# controller_board.net
KiCad netlist of a schematic drawn in EAGLE
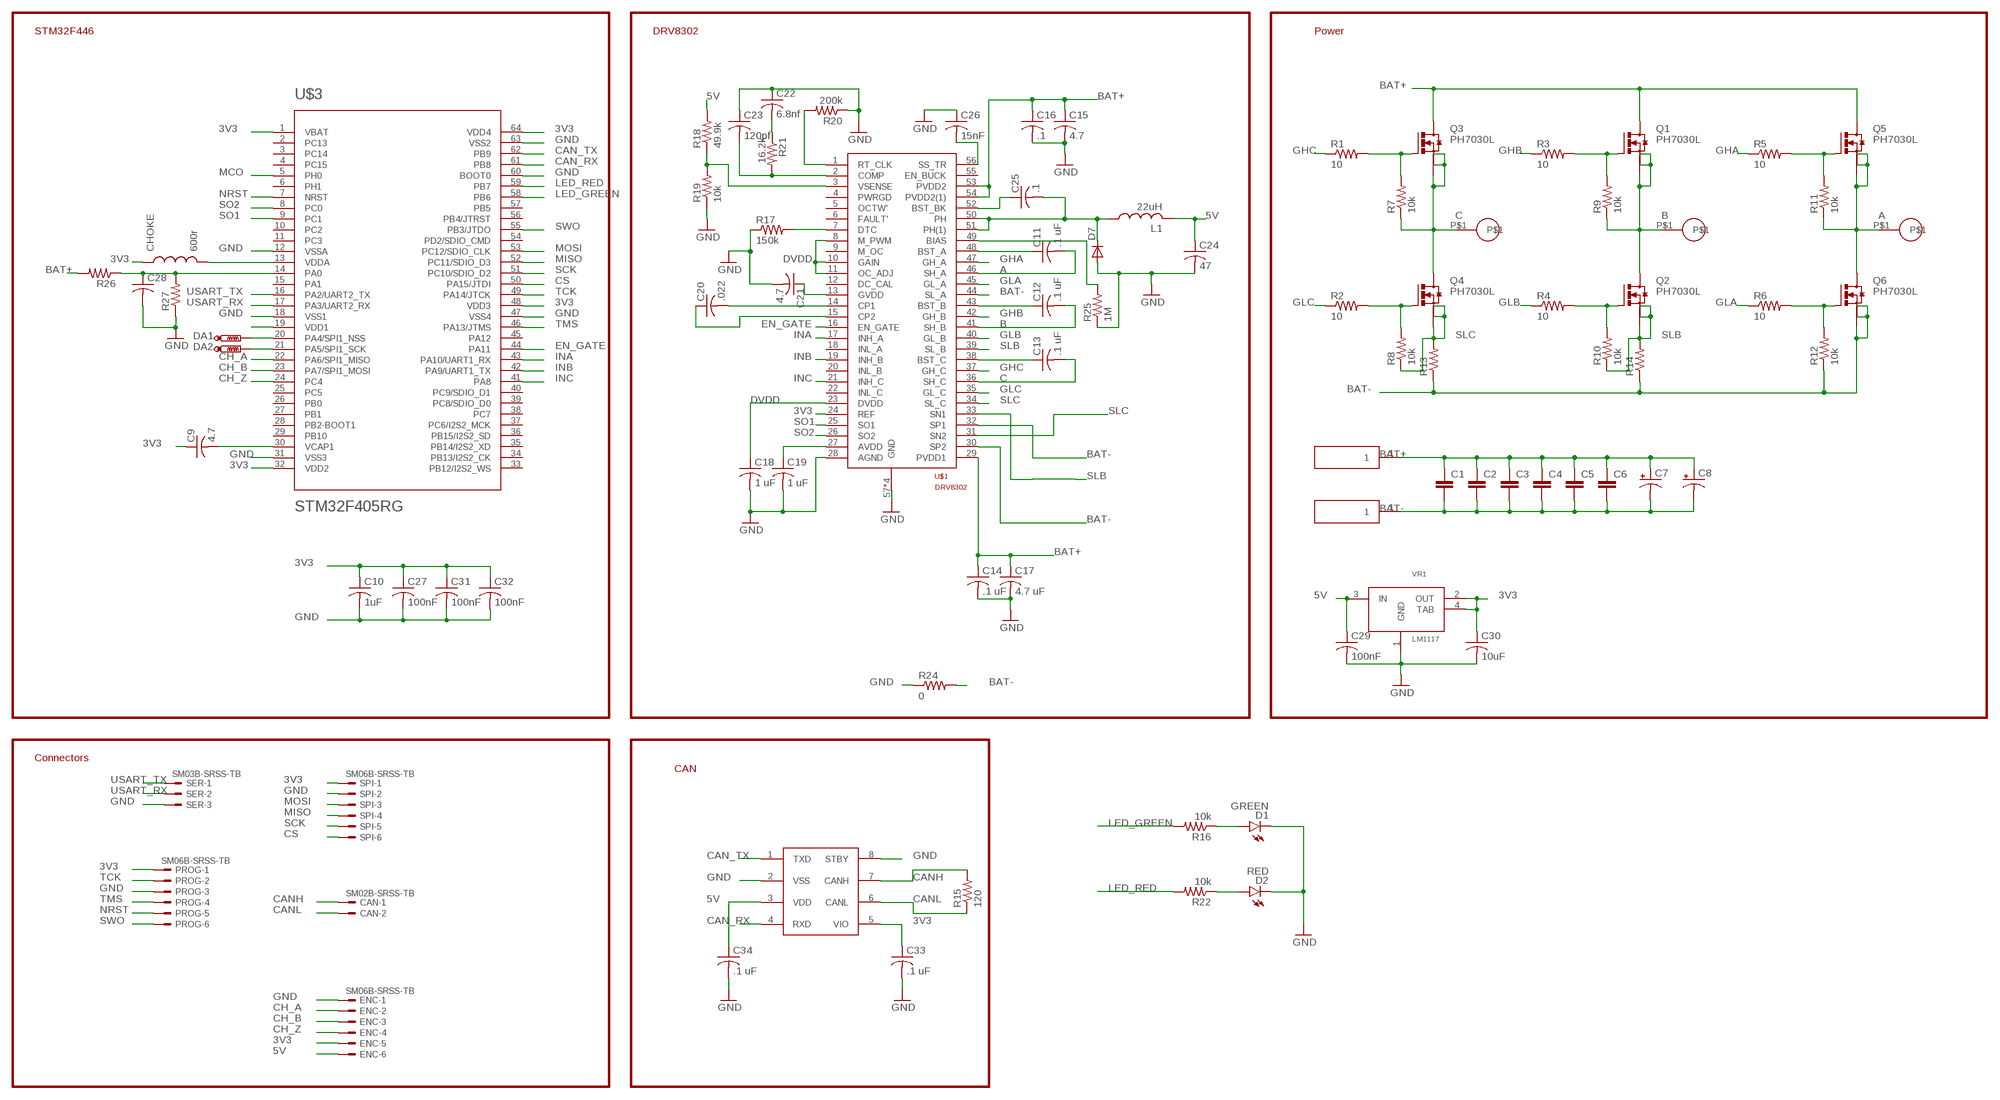
[diagram p0: schematic, sheet 1]

(export (version "E")
  (design (tool "Eeschema 10.0.6"))
  (components
    (comp (ref "C1")
      (value "C-EUC0805")
      (footprint "eagle-import:C0805")
      (libsource (lib "eagle-import") (part "C-EUC0805"))
    )
    (comp (ref "C2")
      (value "C-EUC0805")
      (footprint "eagle-import:C0805")
      (libsource (lib "eagle-import") (part "C-EUC0805"))
    )
    (comp (ref "C3")
      (value "C-EUC0805")
      (footprint "eagle-import:C0805")
      (libsource (lib "eagle-import") (part "C-EUC0805"))
    )
    (comp (ref "C4")
      (value "C-EUC0805")
      (footprint "eagle-import:C0805")
      (libsource (lib "eagle-import") (part "C-EUC0805"))
    )
    (comp (ref "C5")
      (value "C-EUC0805")
      (footprint "eagle-import:C0805")
      (libsource (lib "eagle-import") (part "C-EUC0805"))
    )
    (comp (ref "C6")
      (value "C-EUC0805")
      (footprint "eagle-import:C0805")
      (libsource (lib "eagle-import") (part "C-EUC0805"))
    )
    (comp (ref "C7")
      (value "CPOL-USE3.5-8")
      (footprint "eagle-import:E3,5-8")
      (libsource (lib "eagle-import") (part "CPOL-USE3.5-8"))
    )
    (comp (ref "C8")
      (value "CPOL-USE3.5-8")
      (footprint "eagle-import:E3,5-8")
      (libsource (lib "eagle-import") (part "CPOL-USE3.5-8"))
    )
    (comp (ref "C9")
      (value "4.7")
      (footprint "eagle-import:C0603")
      (libsource (lib "eagle-import") (part "C-USC0603"))
    )
    (comp (ref "C10")
      (value "1uF")
      (footprint "eagle-import:C0603")
      (libsource (lib "eagle-import") (part "C-USC0603"))
    )
    (comp (ref "C11")
      (value ".1 uF")
      (footprint "eagle-import:C0603")
      (libsource (lib "eagle-import") (part "C-USC0603"))
    )
    (comp (ref "C12")
      (value ".1 uF")
      (footprint "eagle-import:C0603")
      (libsource (lib "eagle-import") (part "C-USC0603"))
    )
    (comp (ref "C13")
      (value ".1 uF")
      (footprint "eagle-import:C0603")
      (libsource (lib "eagle-import") (part "C-USC0603"))
    )
    (comp (ref "C14")
      (value ".1 uF")
      (footprint "eagle-import:C0603")
      (libsource (lib "eagle-import") (part "C-USC0603"))
    )
    (comp (ref "C15")
      (value "4.7")
      (footprint "eagle-import:C0805")
      (libsource (lib "eagle-import") (part "C-USC0805"))
    )
    (comp (ref "C16")
      (value ".1")
      (footprint "eagle-import:C0603")
      (libsource (lib "eagle-import") (part "C-USC0603"))
    )
    (comp (ref "C17")
      (value "4.7 uF")
      (footprint "eagle-import:C0805")
      (libsource (lib "eagle-import") (part "C-USC0805"))
    )
    (comp (ref "C18")
      (value "1 uF")
      (footprint "eagle-import:C0603")
      (libsource (lib "eagle-import") (part "C-USC0603"))
    )
    (comp (ref "C19")
      (value "1 uF")
      (footprint "eagle-import:C0603")
      (libsource (lib "eagle-import") (part "C-USC0603"))
    )
    (comp (ref "C20")
      (value ".022")
      (footprint "eagle-import:C0603")
      (libsource (lib "eagle-import") (part "C-USC0603"))
    )
    (comp (ref "C21")
      (value "4.7")
      (footprint "eagle-import:C0805")
      (libsource (lib "eagle-import") (part "C-USC0805"))
    )
    (comp (ref "C22")
      (value "6.8nf")
      (footprint "eagle-import:C0603")
      (libsource (lib "eagle-import") (part "C-USC0603"))
    )
    (comp (ref "C23")
      (value "120pf")
      (footprint "eagle-import:C0603")
      (libsource (lib "eagle-import") (part "C-USC0603"))
    )
    (comp (ref "C24")
      (value "47")
      (footprint "eagle-import:C1210")
      (libsource (lib "eagle-import") (part "C-USC1210"))
    )
    (comp (ref "C25")
      (value ".1")
      (footprint "eagle-import:C0603")
      (libsource (lib "eagle-import") (part "C-USC0603"))
    )
    (comp (ref "C26")
      (value "15nF")
      (footprint "eagle-import:C0603")
      (libsource (lib "eagle-import") (part "C-USC0603"))
    )
    (comp (ref "C27")
      (value "100nF")
      (footprint "eagle-import:C0603")
      (libsource (lib "eagle-import") (part "C-USC0603"))
    )
    (comp (ref "C28")
      (value "C-USC0603")
      (footprint "eagle-import:C0603")
      (libsource (lib "eagle-import") (part "C-USC0603"))
    )
    (comp (ref "C29")
      (value "100nF")
      (footprint "eagle-import:C0603")
      (libsource (lib "eagle-import") (part "C-USC0603"))
    )
    (comp (ref "C30")
      (value "10uF")
      (footprint "eagle-import:C0603")
      (libsource (lib "eagle-import") (part "C-USC0603"))
    )
    (comp (ref "C31")
      (value "100nF")
      (footprint "eagle-import:C0603")
      (libsource (lib "eagle-import") (part "C-USC0603"))
    )
    (comp (ref "C32")
      (value "100nF")
      (footprint "eagle-import:C0603")
      (libsource (lib "eagle-import") (part "C-USC0603"))
    )
    (comp (ref "C33")
      (value ".1 uF")
      (footprint "eagle-import:C0603K")
      (libsource (lib "eagle-import") (part "C-USC0603K"))
    )
    (comp (ref "C34")
      (value ".1 uF")
      (footprint "eagle-import:C0603K")
      (libsource (lib "eagle-import") (part "C-USC0603K"))
    )
    (comp (ref "CAN")
      (value "SM02B-SRSS-TB")
      (footprint "eagle-import:SM02B-SRSS-TB")
      (libsource (lib "eagle-import") (part "?M02B-SRSS-TBS"))
    )
    (comp (ref "CHOKE")
      (value "600r")
      (footprint "eagle-import:0603")
      (libsource (lib "eagle-import") (part "INDUCTOR0603"))
    )
    (comp (ref "D1")
      (value "GREEN")
      (footprint "eagle-import:LED-0603")
      (libsource (lib "eagle-import") (part "LED0603"))
    )
    (comp (ref "D2")
      (value "RED")
      (footprint "eagle-import:LED-0603")
      (libsource (lib "eagle-import") (part "LED0603"))
    )
    (comp (ref "D7")
      (value "DIODE-DO-214AC")
      (footprint "eagle-import:DO-214AC")
      (libsource (lib "eagle-import") (part "DIODE-DO-214AC"))
    )
    (comp (ref "DA1")
      (value "PTR1TP12R")
      (footprint "eagle-import:TP12R")
      (libsource (lib "eagle-import") (part "PTR1TP12R"))
    )
    (comp (ref "DA2")
      (value "PTR1TP12R")
      (footprint "eagle-import:TP12R")
      (libsource (lib "eagle-import") (part "PTR1TP12R"))
    )
    (comp (ref "ENC")
      (value "SM06B-SRSS-TB")
      (footprint "eagle-import:SM06B-SRSS-TB")
      (libsource (lib "eagle-import") (part "?M06B-SRSS-TBS"))
    )
    (comp (ref "J4")
      (value "0.125_PAD")
      (footprint "eagle-import:0.125_PAD")
      (libsource (lib "eagle-import") (part "0.125_PAD"))
    )
    (comp (ref "J5")
      (value "0.125_PAD")
      (footprint "eagle-import:0.125_PAD")
      (libsource (lib "eagle-import") (part "0.125_PAD"))
    )
    (comp (ref "L1")
      (value "22uH")
      (footprint "eagle-import:L4532P")
      (libsource (lib "eagle-import") (part "L-USL4532P"))
    )
    (comp (ref "PROG")
      (value "SM06B-SRSS-TB")
      (footprint "eagle-import:SM06B-SRSS-TB")
      (libsource (lib "eagle-import") (part "?M06B-SRSS-TBS"))
    )
    (comp (ref "Q1")
      (value "PH7030L")
      (footprint "eagle-import:SOT669")
      (libsource (lib "eagle-import") (part "PH7030L"))
    )
    (comp (ref "Q2")
      (value "PH7030L")
      (footprint "eagle-import:SOT669")
      (libsource (lib "eagle-import") (part "PH7030L"))
    )
    (comp (ref "Q3")
      (value "PH7030L")
      (footprint "eagle-import:SOT669")
      (libsource (lib "eagle-import") (part "PH7030L"))
    )
    (comp (ref "Q4")
      (value "PH7030L")
      (footprint "eagle-import:SOT669")
      (libsource (lib "eagle-import") (part "PH7030L"))
    )
    (comp (ref "Q5")
      (value "PH7030L")
      (footprint "eagle-import:SOT669")
      (libsource (lib "eagle-import") (part "PH7030L"))
    )
    (comp (ref "Q6")
      (value "PH7030L")
      (footprint "eagle-import:SOT669")
      (libsource (lib "eagle-import") (part "PH7030L"))
    )
    (comp (ref "R1")
      (value "10")
      (footprint "eagle-import:R0603")
      (libsource (lib "eagle-import") (part "R-US_R0603"))
    )
    (comp (ref "R2")
      (value "10")
      (footprint "eagle-import:R0603")
      (libsource (lib "eagle-import") (part "R-US_R0603"))
    )
    (comp (ref "R3")
      (value "10")
      (footprint "eagle-import:R0603")
      (libsource (lib "eagle-import") (part "R-US_R0603"))
    )
    (comp (ref "R4")
      (value "10")
      (footprint "eagle-import:R0603")
      (libsource (lib "eagle-import") (part "R-US_R0603"))
    )
    (comp (ref "R5")
      (value "10")
      (footprint "eagle-import:R0603")
      (libsource (lib "eagle-import") (part "R-US_R0603"))
    )
    (comp (ref "R6")
      (value "10")
      (footprint "eagle-import:R0603")
      (libsource (lib "eagle-import") (part "R-US_R0603"))
    )
    (comp (ref "R7")
      (value "10k")
      (footprint "eagle-import:R0603")
      (libsource (lib "eagle-import") (part "R-US_R0603"))
    )
    (comp (ref "R8")
      (value "10k")
      (footprint "eagle-import:R0603")
      (libsource (lib "eagle-import") (part "R-US_R0603"))
    )
    (comp (ref "R9")
      (value "10k")
      (footprint "eagle-import:R0603")
      (libsource (lib "eagle-import") (part "R-US_R0603"))
    )
    (comp (ref "R10")
      (value "10k")
      (footprint "eagle-import:R0603")
      (libsource (lib "eagle-import") (part "R-US_R0603"))
    )
    (comp (ref "R11")
      (value "10k")
      (footprint "eagle-import:R0603")
      (libsource (lib "eagle-import") (part "R-US_R0603"))
    )
    (comp (ref "R12")
      (value "10k")
      (footprint "eagle-import:R0603")
      (libsource (lib "eagle-import") (part "R-US_R0603"))
    )
    (comp (ref "R13")
      (value "R-US_R1210")
      (footprint "eagle-import:R1210")
      (libsource (lib "eagle-import") (part "R-US_R1210"))
    )
    (comp (ref "R14")
      (value "R-US_R1210")
      (footprint "eagle-import:R1210")
      (libsource (lib "eagle-import") (part "R-US_R1210"))
    )
    (comp (ref "R15")
      (value "120")
      (footprint "eagle-import:R0603")
      (libsource (lib "eagle-import") (part "R-US_R0603"))
    )
    (comp (ref "R16")
      (value "10k")
      (footprint "eagle-import:R0603")
      (libsource (lib "eagle-import") (part "R-US_R0603"))
    )
    (comp (ref "R17")
      (value "150k")
      (footprint "eagle-import:R0603")
      (libsource (lib "eagle-import") (part "R-US_R0603"))
    )
    (comp (ref "R18")
      (value "49.9k")
      (footprint "eagle-import:R0603")
      (libsource (lib "eagle-import") (part "R-US_R0603"))
    )
    (comp (ref "R19")
      (value "10k")
      (footprint "eagle-import:R0603")
      (libsource (lib "eagle-import") (part "R-US_R0603"))
    )
    (comp (ref "R20")
      (value "200k")
      (footprint "eagle-import:R0603")
      (libsource (lib "eagle-import") (part "R-US_R0603"))
    )
    (comp (ref "R21")
      (value "16.2k")
      (footprint "eagle-import:R0603")
      (libsource (lib "eagle-import") (part "R-US_R0603"))
    )
    (comp (ref "R22")
      (value "10k")
      (footprint "eagle-import:R0603")
      (libsource (lib "eagle-import") (part "R-US_R0603"))
    )
    (comp (ref "R24")
      (value "0")
      (footprint "eagle-import:R0603")
      (libsource (lib "eagle-import") (part "R-US_R0603"))
    )
    (comp (ref "R25")
      (value "1M")
      (footprint "eagle-import:R0603")
      (libsource (lib "eagle-import") (part "R-US_R0603"))
    )
    (comp (ref "R26")
      (value "R-US_R0603")
      (footprint "eagle-import:R0603")
      (libsource (lib "eagle-import") (part "R-US_R0603"))
    )
    (comp (ref "R27")
      (value "R-US_R0603")
      (footprint "eagle-import:R0603")
      (libsource (lib "eagle-import") (part "R-US_R0603"))
    )
    (comp (ref "SER")
      (value "SM03B-SRSS-TB")
      (footprint "eagle-import:SM03B-SRSS-TB")
      (libsource (lib "eagle-import") (part "?M03B-SRSS-TBS"))
    )
    (comp (ref "SPI")
      (value "SM06B-SRSS-TB")
      (footprint "eagle-import:SM06B-SRSS-TB")
      (libsource (lib "eagle-import") (part "?M06B-SRSS-TBS"))
    )
    (comp (ref "U$1")
      (value "DRV8302")
      (footprint "eagle-import:HTSSOP56")
      (libsource (lib "eagle-import") (part "DRV8302"))
    )
    (comp (ref "U$2")
      (value "18_AWG_PAD")
      (footprint "eagle-import:18_AWG_PAD")
      (libsource (lib "eagle-import") (part "18_AWG_PAD"))
    )
    (comp (ref "U$3")
      (value "STM32F405RG")
      (footprint "eagle-import:TQFP64")
      (libsource (lib "eagle-import") (part "STM32F405RG"))
    )
    (comp (ref "U$4")
      (value "18_AWG_PAD")
      (footprint "eagle-import:18_AWG_PAD")
      (libsource (lib "eagle-import") (part "18_AWG_PAD"))
    )
    (comp (ref "U$5")
      (value "18_AWG_PAD")
      (footprint "eagle-import:18_AWG_PAD")
      (libsource (lib "eagle-import") (part "18_AWG_PAD"))
    )
    (comp (ref "U$6")
      (value "MCP2561")
      (footprint "eagle-import:SO08")
      (libsource (lib "eagle-import") (part "MCP2561"))
    )
    (comp (ref "VR1")
      (value "LM1117")
      (footprint "eagle-import:SOT-223")
      (libsource (lib "eagle-import") (part "LM1117"))
    )
  )
  (nets
    (net (code "1") (name "/3V3") (class "Default")
      (node (ref "C10") (pin "1") (pinfunction "1_1") (pintype "passive"))
      (node (ref "C27") (pin "1") (pinfunction "1_1") (pintype "passive"))
      (node (ref "C30") (pin "1") (pinfunction "1_1") (pintype "passive"))
      (node (ref "C31") (pin "1") (pinfunction "1_1") (pintype "passive"))
      (node (ref "C32") (pin "1") (pinfunction "1_1") (pintype "passive"))
      (node (ref "C33") (pin "1") (pinfunction "1_1") (pintype "passive"))
      (node (ref "C9") (pin "1") (pinfunction "1_1") (pintype "passive"))
      (node (ref "CHOKE") (pin "1") (pinfunction "1_1") (pintype "passive"))
      (node (ref "ENC") (pin "5") (pinfunction "S_5") (pintype "passive"))
      (node (ref "PROG") (pin "1") (pinfunction "S_1") (pintype "passive"))
      (node (ref "SPI") (pin "1") (pinfunction "S_1") (pintype "passive"))
      (node (ref "U$1") (pin "24") (pinfunction "REF_24") (pintype "bidirectional"))
      (node (ref "U$3") (pin "1") (pinfunction "VBAT_1") (pintype "bidirectional"))
      (node (ref "U$3") (pin "19") (pinfunction "VDD1_19") (pintype "bidirectional"))
      (node (ref "U$3") (pin "32") (pinfunction "VDD2_32") (pintype "bidirectional"))
      (node (ref "U$3") (pin "48") (pinfunction "VDD3_48") (pintype "bidirectional"))
      (node (ref "U$3") (pin "64") (pinfunction "VDD4_64") (pintype "bidirectional"))
      (node (ref "U$6") (pin "5") (pinfunction "VIO_5") (pintype "bidirectional"))
      (node (ref "VR1") (pin "2") (pinfunction "OUT_2") (pintype "bidirectional"))
      (node (ref "VR1") (pin "4") (pinfunction "TAB_4") (pintype "bidirectional"))
    )
    (net (code "2") (name "/5V") (class "Default")
      (node (ref "C24") (pin "1") (pinfunction "1_1") (pintype "passive"))
      (node (ref "C29") (pin "1") (pinfunction "1_1") (pintype "passive"))
      (node (ref "C34") (pin "1") (pinfunction "1_1") (pintype "passive"))
      (node (ref "ENC") (pin "6") (pinfunction "S_6") (pintype "passive"))
      (node (ref "L1") (pin "2") (pinfunction "2_2") (pintype "passive"))
      (node (ref "R18") (pin "2") (pinfunction "2_2") (pintype "passive"))
      (node (ref "U$6") (pin "3") (pinfunction "VDD_3") (pintype "bidirectional"))
      (node (ref "VR1") (pin "3") (pinfunction "IN_3") (pintype "bidirectional"))
    )
    (net (code "3") (name "/A") (class "Default")
      (node (ref "C11") (pin "2") (pinfunction "2_2") (pintype "passive"))
      (node (ref "Q5") (pin "1") (pinfunction "S_1") (pintype "passive"))
      (node (ref "Q5") (pin "2") (pinfunction "S_2") (pintype "passive"))
      (node (ref "Q5") (pin "3") (pinfunction "S_3") (pintype "passive"))
      (node (ref "Q6") (pin "MB") (pinfunction "D_MB") (pintype "passive"))
      (node (ref "R11") (pin "1") (pinfunction "1_1") (pintype "passive"))
      (node (ref "U$1") (pin "46") (pinfunction "SH_A_46") (pintype "bidirectional"))
      (node (ref "U$5") (pin "P$1") (pinfunction "P$1_P$1") (pintype "bidirectional"))
    )
    (net (code "4") (name "/B") (class "Default")
      (node (ref "C12") (pin "2") (pinfunction "2_2") (pintype "passive"))
      (node (ref "Q1") (pin "1") (pinfunction "S_1") (pintype "passive"))
      (node (ref "Q1") (pin "2") (pinfunction "S_2") (pintype "passive"))
      (node (ref "Q1") (pin "3") (pinfunction "S_3") (pintype "passive"))
      (node (ref "Q2") (pin "MB") (pinfunction "D_MB") (pintype "passive"))
      (node (ref "R9") (pin "1") (pinfunction "1_1") (pintype "passive"))
      (node (ref "U$1") (pin "41") (pinfunction "SH_B_41") (pintype "bidirectional"))
      (node (ref "U$4") (pin "P$1") (pinfunction "P$1_P$1") (pintype "bidirectional"))
    )
    (net (code "5") (name "/BAT+") (class "Default")
      (node (ref "C1") (pin "1") (pinfunction "1_1") (pintype "passive"))
      (node (ref "C14") (pin "1") (pinfunction "1_1") (pintype "passive"))
      (node (ref "C15") (pin "1") (pinfunction "1_1") (pintype "passive"))
      (node (ref "C16") (pin "1") (pinfunction "1_1") (pintype "passive"))
      (node (ref "C17") (pin "1") (pinfunction "1_1") (pintype "passive"))
      (node (ref "C2") (pin "1") (pinfunction "1_1") (pintype "passive"))
      (node (ref "C3") (pin "1") (pinfunction "1_1") (pintype "passive"))
      (node (ref "C4") (pin "1") (pinfunction "1_1") (pintype "passive"))
      (node (ref "C5") (pin "1") (pinfunction "1_1") (pintype "passive"))
      (node (ref "C6") (pin "1") (pinfunction "1_1") (pintype "passive"))
      (node (ref "C7") (pin "+") (pinfunction "+_+") (pintype "passive"))
      (node (ref "C8") (pin "+") (pinfunction "+_+") (pintype "passive"))
      (node (ref "J4") (pin "1") (pinfunction "1_1") (pintype "bidirectional"))
      (node (ref "Q1") (pin "MB") (pinfunction "D_MB") (pintype "passive"))
      (node (ref "Q3") (pin "MB") (pinfunction "D_MB") (pintype "passive"))
      (node (ref "Q5") (pin "MB") (pinfunction "D_MB") (pintype "passive"))
      (node (ref "R26") (pin "2") (pinfunction "2_2") (pintype "passive"))
      (node (ref "U$1") (pin "29") (pinfunction "PVDD1_29") (pintype "bidirectional"))
      (node (ref "U$1") (pin "53") (pinfunction "PVDD2_53") (pintype "bidirectional"))
      (node (ref "U$1") (pin "54") (pinfunction "PVDD2(1)_54") (pintype "bidirectional"))
    )
    (net (code "6") (name "/BAT-") (class "Default")
      (node (ref "C1") (pin "2") (pinfunction "2_2") (pintype "passive"))
      (node (ref "C2") (pin "2") (pinfunction "2_2") (pintype "passive"))
      (node (ref "C3") (pin "2") (pinfunction "2_2") (pintype "passive"))
      (node (ref "C4") (pin "2") (pinfunction "2_2") (pintype "passive"))
      (node (ref "C5") (pin "2") (pinfunction "2_2") (pintype "passive"))
      (node (ref "C6") (pin "2") (pinfunction "2_2") (pintype "passive"))
      (node (ref "C7") (pin "-") (pinfunction "-_-") (pintype "passive"))
      (node (ref "C8") (pin "-") (pinfunction "-_-") (pintype "passive"))
      (node (ref "J5") (pin "1") (pinfunction "1_1") (pintype "bidirectional"))
      (node (ref "Q6") (pin "1") (pinfunction "S_1") (pintype "passive"))
      (node (ref "Q6") (pin "2") (pinfunction "S_2") (pintype "passive"))
      (node (ref "Q6") (pin "3") (pinfunction "S_3") (pintype "passive"))
      (node (ref "R12") (pin "1") (pinfunction "1_1") (pintype "passive"))
      (node (ref "R13") (pin "1") (pinfunction "1_1") (pintype "passive"))
      (node (ref "R14") (pin "1") (pinfunction "1_1") (pintype "passive"))
      (node (ref "R24") (pin "2") (pinfunction "2_2") (pintype "passive"))
      (node (ref "U$1") (pin "30") (pinfunction "SP2_30") (pintype "bidirectional"))
      (node (ref "U$1") (pin "32") (pinfunction "SP1_32") (pintype "bidirectional"))
      (node (ref "U$1") (pin "44") (pinfunction "SL_A_44") (pintype "bidirectional"))
    )
    (net (code "7") (name "/C") (class "Default")
      (node (ref "C13") (pin "2") (pinfunction "2_2") (pintype "passive"))
      (node (ref "Q3") (pin "1") (pinfunction "S_1") (pintype "passive"))
      (node (ref "Q3") (pin "2") (pinfunction "S_2") (pintype "passive"))
      (node (ref "Q3") (pin "3") (pinfunction "S_3") (pintype "passive"))
      (node (ref "Q4") (pin "MB") (pinfunction "D_MB") (pintype "passive"))
      (node (ref "R7") (pin "1") (pinfunction "1_1") (pintype "passive"))
      (node (ref "U$1") (pin "36") (pinfunction "SH_C_36") (pintype "bidirectional"))
      (node (ref "U$2") (pin "P$1") (pinfunction "P$1_P$1") (pintype "bidirectional"))
    )
    (net (code "8") (name "/CANH") (class "Default")
      (node (ref "CAN") (pin "1") (pinfunction "S_1") (pintype "passive"))
      (node (ref "R15") (pin "2") (pinfunction "2_2") (pintype "passive"))
      (node (ref "U$6") (pin "7") (pinfunction "CANH_7") (pintype "bidirectional"))
    )
    (net (code "9") (name "/CANL") (class "Default")
      (node (ref "CAN") (pin "2") (pinfunction "S_2") (pintype "passive"))
      (node (ref "R15") (pin "1") (pinfunction "1_1") (pintype "passive"))
      (node (ref "U$6") (pin "6") (pinfunction "CANL_6") (pintype "bidirectional"))
    )
    (net (code "10") (name "/CAN_RX") (class "Default")
      (node (ref "U$3") (pin "61") (pinfunction "PB8_61") (pintype "bidirectional"))
      (node (ref "U$6") (pin "4") (pinfunction "RXD_4") (pintype "bidirectional"))
    )
    (net (code "11") (name "/CAN_TX") (class "Default")
      (node (ref "U$3") (pin "62") (pinfunction "PB9_62") (pintype "bidirectional"))
      (node (ref "U$6") (pin "1") (pinfunction "TXD_1") (pintype "bidirectional"))
    )
    (net (code "12") (name "/CH_A") (class "Default")
      (node (ref "ENC") (pin "2") (pinfunction "S_2") (pintype "passive"))
      (node (ref "U$3") (pin "22") (pinfunction "PA6/SPI1_MISO_22") (pintype "bidirectional"))
    )
    (net (code "13") (name "/CH_B") (class "Default")
      (node (ref "ENC") (pin "3") (pinfunction "S_3") (pintype "passive"))
      (node (ref "U$3") (pin "23") (pinfunction "PA7/SPI1_MOSI_23") (pintype "bidirectional"))
    )
    (net (code "14") (name "/CH_Z") (class "Default")
      (node (ref "ENC") (pin "4") (pinfunction "S_4") (pintype "passive"))
      (node (ref "U$3") (pin "24") (pinfunction "PC4_24") (pintype "bidirectional"))
    )
    (net (code "15") (name "/CS") (class "Default")
      (node (ref "SPI") (pin "6") (pinfunction "S_6") (pintype "passive"))
      (node (ref "U$3") (pin "50") (pinfunction "PA15/JTDI_50") (pintype "bidirectional"))
    )
    (net (code "16") (name "/DVDD") (class "Default")
      (node (ref "C18") (pin "1") (pinfunction "1_1") (pintype "passive"))
      (node (ref "U$1") (pin "10") (pinfunction "GAIN_10") (pintype "bidirectional"))
      (node (ref "U$1") (pin "11") (pinfunction "OC_ADJ_11") (pintype "bidirectional"))
      (node (ref "U$1") (pin "23") (pinfunction "DVDD_23") (pintype "bidirectional"))
      (node (ref "U$1") (pin "8") (pinfunction "M_PWM_8") (pintype "bidirectional"))
    )
    (net (code "17") (name "/EN_GATE") (class "Default")
      (node (ref "U$1") (pin "16") (pinfunction "EN_GATE_16") (pintype "bidirectional"))
      (node (ref "U$3") (pin "44") (pinfunction "PA11_44") (pintype "bidirectional"))
    )
    (net (code "18") (name "/GHA") (class "Default")
      (node (ref "R5") (pin "1") (pinfunction "1_1") (pintype "passive"))
      (node (ref "U$1") (pin "47") (pinfunction "GH_A_47") (pintype "bidirectional"))
    )
    (net (code "19") (name "/GHB") (class "Default")
      (node (ref "R3") (pin "1") (pinfunction "1_1") (pintype "passive"))
      (node (ref "U$1") (pin "42") (pinfunction "GH_B_42") (pintype "bidirectional"))
    )
    (net (code "20") (name "/GHC") (class "Default")
      (node (ref "R1") (pin "1") (pinfunction "1_1") (pintype "passive"))
      (node (ref "U$1") (pin "37") (pinfunction "GH_C_37") (pintype "bidirectional"))
    )
    (net (code "21") (name "/GLA") (class "Default")
      (node (ref "R6") (pin "1") (pinfunction "1_1") (pintype "passive"))
      (node (ref "U$1") (pin "45") (pinfunction "GL_A_45") (pintype "bidirectional"))
    )
    (net (code "22") (name "/GLB") (class "Default")
      (node (ref "R4") (pin "1") (pinfunction "1_1") (pintype "passive"))
      (node (ref "U$1") (pin "40") (pinfunction "GL_B_40") (pintype "bidirectional"))
    )
    (net (code "23") (name "/GLC") (class "Default")
      (node (ref "R2") (pin "1") (pinfunction "1_1") (pintype "passive"))
      (node (ref "U$1") (pin "35") (pinfunction "GL_C_35") (pintype "bidirectional"))
    )
    (net (code "24") (name "/INA") (class "Default")
      (node (ref "U$1") (pin "17") (pinfunction "INH_A_17") (pintype "bidirectional"))
      (node (ref "U$3") (pin "43") (pinfunction "PA10/UART1_RX_43") (pintype "bidirectional"))
    )
    (net (code "25") (name "/INB") (class "Default")
      (node (ref "U$1") (pin "19") (pinfunction "INH_B_19") (pintype "bidirectional"))
      (node (ref "U$3") (pin "42") (pinfunction "PA9/UART1_TX_42") (pintype "bidirectional"))
    )
    (net (code "26") (name "/INC") (class "Default")
      (node (ref "U$1") (pin "21") (pinfunction "INH_C_21") (pintype "bidirectional"))
      (node (ref "U$3") (pin "41") (pinfunction "PA8_41") (pintype "bidirectional"))
    )
    (net (code "27") (name "/LED_GREEN") (class "Default")
      (node (ref "R16") (pin "2") (pinfunction "2_2") (pintype "passive"))
      (node (ref "U$3") (pin "58") (pinfunction "PB6_58") (pintype "bidirectional"))
    )
    (net (code "28") (name "/LED_RED") (class "Default")
      (node (ref "R22") (pin "2") (pinfunction "2_2") (pintype "passive"))
      (node (ref "U$3") (pin "59") (pinfunction "PB7_59") (pintype "bidirectional"))
    )
    (net (code "29") (name "/MCO") (class "Default")
      (node (ref "U$3") (pin "5") (pinfunction "PH0_5") (pintype "bidirectional"))
    )
    (net (code "30") (name "/MISO") (class "Default")
      (node (ref "SPI") (pin "4") (pinfunction "S_4") (pintype "passive"))
      (node (ref "U$3") (pin "52") (pinfunction "PC11/SDIO_D3_52") (pintype "bidirectional"))
    )
    (net (code "31") (name "/MOSI") (class "Default")
      (node (ref "SPI") (pin "3") (pinfunction "S_3") (pintype "passive"))
      (node (ref "U$3") (pin "53") (pinfunction "PC12/SDIO_CLK_53") (pintype "bidirectional"))
    )
    (net (code "32") (name "/NRST") (class "Default")
      (node (ref "PROG") (pin "5") (pinfunction "S_5") (pintype "passive"))
      (node (ref "U$3") (pin "7") (pinfunction "NRST_7") (pintype "bidirectional"))
    )
    (net (code "33") (name "/SCK") (class "Default")
      (node (ref "SPI") (pin "5") (pinfunction "S_5") (pintype "passive"))
      (node (ref "U$3") (pin "51") (pinfunction "PC10/SDIO_D2_51") (pintype "bidirectional"))
    )
    (net (code "34") (name "/SLB") (class "Default")
      (node (ref "Q2") (pin "1") (pinfunction "S_1") (pintype "passive"))
      (node (ref "Q2") (pin "2") (pinfunction "S_2") (pintype "passive"))
      (node (ref "Q2") (pin "3") (pinfunction "S_3") (pintype "passive"))
      (node (ref "R10") (pin "1") (pinfunction "1_1") (pintype "passive"))
      (node (ref "R14") (pin "2") (pinfunction "2_2") (pintype "passive"))
      (node (ref "U$1") (pin "33") (pinfunction "SN1_33") (pintype "bidirectional"))
      (node (ref "U$1") (pin "39") (pinfunction "SL_B_39") (pintype "bidirectional"))
    )
    (net (code "35") (name "/SLC") (class "Default")
      (node (ref "Q4") (pin "1") (pinfunction "S_1") (pintype "passive"))
      (node (ref "Q4") (pin "2") (pinfunction "S_2") (pintype "passive"))
      (node (ref "Q4") (pin "3") (pinfunction "S_3") (pintype "passive"))
      (node (ref "R13") (pin "2") (pinfunction "2_2") (pintype "passive"))
      (node (ref "R8") (pin "1") (pinfunction "1_1") (pintype "passive"))
      (node (ref "U$1") (pin "31") (pinfunction "SN2_31") (pintype "bidirectional"))
      (node (ref "U$1") (pin "34") (pinfunction "SL_C_34") (pintype "bidirectional"))
    )
    (net (code "36") (name "/SO1") (class "Default")
      (node (ref "U$1") (pin "25") (pinfunction "SO1_25") (pintype "bidirectional"))
      (node (ref "U$3") (pin "9") (pinfunction "PC1_9") (pintype "bidirectional"))
    )
    (net (code "37") (name "/SO2") (class "Default")
      (node (ref "U$1") (pin "26") (pinfunction "SO2_26") (pintype "bidirectional"))
      (node (ref "U$3") (pin "8") (pinfunction "PC0_8") (pintype "bidirectional"))
    )
    (net (code "38") (name "/SWO") (class "Default")
      (node (ref "PROG") (pin "6") (pinfunction "S_6") (pintype "passive"))
      (node (ref "U$3") (pin "55") (pinfunction "PB3/JTDO_55") (pintype "bidirectional"))
    )
    (net (code "39") (name "/TCK") (class "Default")
      (node (ref "PROG") (pin "2") (pinfunction "S_2") (pintype "passive"))
      (node (ref "U$3") (pin "49") (pinfunction "PA14/JTCK_49") (pintype "bidirectional"))
    )
    (net (code "40") (name "/TMS") (class "Default")
      (node (ref "PROG") (pin "4") (pinfunction "S_4") (pintype "passive"))
      (node (ref "U$3") (pin "46") (pinfunction "PA13/JTMS_46") (pintype "bidirectional"))
    )
    (net (code "41") (name "/USART_RX") (class "Default")
      (node (ref "SER") (pin "2") (pinfunction "S_2") (pintype "passive"))
      (node (ref "U$3") (pin "17") (pinfunction "PA3/UART2_RX_17") (pintype "bidirectional"))
    )
    (net (code "42") (name "/USART_TX") (class "Default")
      (node (ref "SER") (pin "1") (pinfunction "S_1") (pintype "passive"))
      (node (ref "U$3") (pin "16") (pinfunction "PA2/UART2_TX_16") (pintype "bidirectional"))
    )
    (net (code "43") (name "GND") (class "Default")
      (node (ref "C10") (pin "2") (pinfunction "2_2") (pintype "passive"))
      (node (ref "C14") (pin "2") (pinfunction "2_2") (pintype "passive"))
      (node (ref "C15") (pin "2") (pinfunction "2_2") (pintype "passive"))
      (node (ref "C16") (pin "2") (pinfunction "2_2") (pintype "passive"))
      (node (ref "C17") (pin "2") (pinfunction "2_2") (pintype "passive"))
      (node (ref "C18") (pin "2") (pinfunction "2_2") (pintype "passive"))
      (node (ref "C19") (pin "2") (pinfunction "2_2") (pintype "passive"))
      (node (ref "C21") (pin "2") (pinfunction "2_2") (pintype "passive"))
      (node (ref "C22") (pin "1") (pinfunction "1_1") (pintype "passive"))
      (node (ref "C23") (pin "1") (pinfunction "1_1") (pintype "passive"))
      (node (ref "C24") (pin "2") (pinfunction "2_2") (pintype "passive"))
      (node (ref "C26") (pin "1") (pinfunction "1_1") (pintype "passive"))
      (node (ref "C27") (pin "2") (pinfunction "2_2") (pintype "passive"))
      (node (ref "C28") (pin "2") (pinfunction "2_2") (pintype "passive"))
      (node (ref "C29") (pin "2") (pinfunction "2_2") (pintype "passive"))
      (node (ref "C30") (pin "2") (pinfunction "2_2") (pintype "passive"))
      (node (ref "C31") (pin "2") (pinfunction "2_2") (pintype "passive"))
      (node (ref "C32") (pin "2") (pinfunction "2_2") (pintype "passive"))
      (node (ref "C33") (pin "2") (pinfunction "2_2") (pintype "passive"))
      (node (ref "C34") (pin "2") (pinfunction "2_2") (pintype "passive"))
      (node (ref "D1") (pin "C") (pinfunction "C_C") (pintype "passive"))
      (node (ref "D2") (pin "C") (pinfunction "C_C") (pintype "passive"))
      (node (ref "D7") (pin "A") (pinfunction "A_A") (pintype "passive"))
      (node (ref "ENC") (pin "1") (pinfunction "S_1") (pintype "passive"))
      (node (ref "PROG") (pin "3") (pinfunction "S_3") (pintype "passive"))
      (node (ref "R17") (pin "1") (pinfunction "1_1") (pintype "passive"))
      (node (ref "R19") (pin "1") (pinfunction "1_1") (pintype "passive"))
      (node (ref "R20") (pin "1") (pinfunction "1_1") (pintype "passive"))
      (node (ref "R24") (pin "1") (pinfunction "1_1") (pintype "passive"))
      (node (ref "R25") (pin "1") (pinfunction "1_1") (pintype "passive"))
      (node (ref "R27") (pin "1") (pinfunction "1_1") (pintype "passive"))
      (node (ref "SER") (pin "3") (pinfunction "S_3") (pintype "passive"))
      (node (ref "SPI") (pin "2") (pinfunction "S_2") (pintype "passive"))
      (node (ref "U$1") (pin "28") (pinfunction "AGND_28") (pintype "bidirectional"))
      (node (ref "U$1") (pin "57") (pinfunction "GND_57") (pintype "bidirectional"))
      (node (ref "U$1") (pin "P$1") (pinfunction "GND_P$1") (pintype "bidirectional"))
      (node (ref "U$1") (pin "P$2") (pinfunction "GND_P$2") (pintype "bidirectional"))
      (node (ref "U$1") (pin "P$3") (pinfunction "GND_P$3") (pintype "bidirectional"))
      (node (ref "U$3") (pin "12") (pinfunction "VSSA_12") (pintype "bidirectional"))
      (node (ref "U$3") (pin "18") (pinfunction "VSS1_18") (pintype "bidirectional"))
      (node (ref "U$3") (pin "31") (pinfunction "VSS3_31") (pintype "bidirectional"))
      (node (ref "U$3") (pin "47") (pinfunction "VSS4_47") (pintype "bidirectional"))
      (node (ref "U$3") (pin "60") (pinfunction "BOOT0_60") (pintype "bidirectional"))
      (node (ref "U$3") (pin "63") (pinfunction "VSS2_63") (pintype "bidirectional"))
      (node (ref "U$6") (pin "2") (pinfunction "VSS_2") (pintype "bidirectional"))
      (node (ref "U$6") (pin "8") (pinfunction "STBY_8") (pintype "bidirectional"))
      (node (ref "VR1") (pin "1") (pinfunction "GND_1") (pintype "bidirectional"))
    )
    (net (code "44") (name "Net-(C22-Pad2)") (class "Default")
      (node (ref "C22") (pin "2") (pinfunction "2_2") (pintype "passive"))
      (node (ref "R21") (pin "1") (pinfunction "1_1") (pintype "passive"))
    )
    (net (code "45") (name "Net-(D1-PadA)") (class "Default")
      (node (ref "D1") (pin "A") (pinfunction "A_A") (pintype "passive"))
      (node (ref "R16") (pin "1") (pinfunction "1_1") (pintype "passive"))
    )
    (net (code "46") (name "Net-(D2-PadA)") (class "Default")
      (node (ref "D2") (pin "A") (pinfunction "A_A") (pintype "passive"))
      (node (ref "R22") (pin "1") (pinfunction "1_1") (pintype "passive"))
    )
    (net (code "47") (name "Net-(Q1-G)") (class "Default")
      (node (ref "Q1") (pin "4") (pinfunction "G_4") (pintype "passive"))
      (node (ref "R3") (pin "2") (pinfunction "2_2") (pintype "passive"))
      (node (ref "R9") (pin "2") (pinfunction "2_2") (pintype "passive"))
    )
    (net (code "48") (name "Net-(Q2-G)") (class "Default")
      (node (ref "Q2") (pin "4") (pinfunction "G_4") (pintype "passive"))
      (node (ref "R10") (pin "2") (pinfunction "2_2") (pintype "passive"))
      (node (ref "R4") (pin "2") (pinfunction "2_2") (pintype "passive"))
    )
    (net (code "49") (name "Net-(Q3-G)") (class "Default")
      (node (ref "Q3") (pin "4") (pinfunction "G_4") (pintype "passive"))
      (node (ref "R1") (pin "2") (pinfunction "2_2") (pintype "passive"))
      (node (ref "R7") (pin "2") (pinfunction "2_2") (pintype "passive"))
    )
    (net (code "50") (name "Net-(Q4-G)") (class "Default")
      (node (ref "Q4") (pin "4") (pinfunction "G_4") (pintype "passive"))
      (node (ref "R2") (pin "2") (pinfunction "2_2") (pintype "passive"))
      (node (ref "R8") (pin "2") (pinfunction "2_2") (pintype "passive"))
    )
    (net (code "51") (name "Net-(Q5-G)") (class "Default")
      (node (ref "Q5") (pin "4") (pinfunction "G_4") (pintype "passive"))
      (node (ref "R11") (pin "2") (pinfunction "2_2") (pintype "passive"))
      (node (ref "R5") (pin "2") (pinfunction "2_2") (pintype "passive"))
    )
    (net (code "52") (name "Net-(Q6-G)") (class "Default")
      (node (ref "Q6") (pin "4") (pinfunction "G_4") (pintype "passive"))
      (node (ref "R12") (pin "2") (pinfunction "2_2") (pintype "passive"))
      (node (ref "R6") (pin "2") (pinfunction "2_2") (pintype "passive"))
    )
    (net (code "53") (name "Net-(U$1-AVDD)") (class "Default")
      (node (ref "C19") (pin "1") (pinfunction "1_1") (pintype "passive"))
      (node (ref "U$1") (pin "27") (pinfunction "AVDD_27") (pintype "bidirectional"))
    )
    (net (code "54") (name "Net-(U$1-BIAS)") (class "Default")
      (node (ref "R25") (pin "2") (pinfunction "2_2") (pintype "passive"))
      (node (ref "U$1") (pin "49") (pinfunction "BIAS_49") (pintype "bidirectional"))
    )
    (net (code "55") (name "Net-(U$1-BST_A)") (class "Default")
      (node (ref "C11") (pin "1") (pinfunction "1_1") (pintype "passive"))
      (node (ref "U$1") (pin "48") (pinfunction "BST_A_48") (pintype "bidirectional"))
    )
    (net (code "56") (name "Net-(U$1-BST_B)") (class "Default")
      (node (ref "C12") (pin "1") (pinfunction "1_1") (pintype "passive"))
      (node (ref "U$1") (pin "43") (pinfunction "BST_B_43") (pintype "bidirectional"))
    )
    (net (code "57") (name "Net-(U$1-BST_BK)") (class "Default")
      (node (ref "C25") (pin "1") (pinfunction "1_1") (pintype "passive"))
      (node (ref "U$1") (pin "52") (pinfunction "BST_BK_52") (pintype "bidirectional"))
    )
    (net (code "58") (name "Net-(U$1-BST_C)") (class "Default")
      (node (ref "C13") (pin "1") (pinfunction "1_1") (pintype "passive"))
      (node (ref "U$1") (pin "38") (pinfunction "BST_C_38") (pintype "bidirectional"))
    )
    (net (code "59") (name "Net-(U$1-COMP)") (class "Default")
      (node (ref "C23") (pin "2") (pinfunction "2_2") (pintype "passive"))
      (node (ref "R21") (pin "2") (pinfunction "2_2") (pintype "passive"))
      (node (ref "U$1") (pin "2") (pinfunction "COMP_2") (pintype "bidirectional"))
    )
    (net (code "60") (name "Net-(U$1-CP1)") (class "Default")
      (node (ref "C20") (pin "2") (pinfunction "2_2") (pintype "passive"))
      (node (ref "U$1") (pin "14") (pinfunction "CP1_14") (pintype "bidirectional"))
    )
    (net (code "61") (name "Net-(U$1-CP2)") (class "Default")
      (node (ref "C20") (pin "1") (pinfunction "1_1") (pintype "passive"))
      (node (ref "U$1") (pin "15") (pinfunction "CP2_15") (pintype "bidirectional"))
    )
    (net (code "62") (name "Net-(U$1-DTC)") (class "Default")
      (node (ref "R17") (pin "2") (pinfunction "2_2") (pintype "passive"))
      (node (ref "U$1") (pin "7") (pinfunction "DTC_7") (pintype "bidirectional"))
    )
    (net (code "63") (name "Net-(U$1-GVDD)") (class "Default")
      (node (ref "C21") (pin "1") (pinfunction "1_1") (pintype "passive"))
      (node (ref "U$1") (pin "13") (pinfunction "GVDD_13") (pintype "bidirectional"))
    )
    (net (code "64") (name "Net-(U$1-PH(1))") (class "Default")
      (node (ref "C25") (pin "2") (pinfunction "2_2") (pintype "passive"))
      (node (ref "D7") (pin "C") (pinfunction "C_C") (pintype "passive"))
      (node (ref "L1") (pin "1") (pinfunction "1_1") (pintype "passive"))
      (node (ref "U$1") (pin "50") (pinfunction "PH_50") (pintype "bidirectional"))
      (node (ref "U$1") (pin "51") (pinfunction "PH(1)_51") (pintype "bidirectional"))
    )
    (net (code "65") (name "Net-(U$1-RT_CLK)") (class "Default")
      (node (ref "R20") (pin "2") (pinfunction "2_2") (pintype "passive"))
      (node (ref "U$1") (pin "1") (pinfunction "RT_CLK_1") (pintype "bidirectional"))
    )
    (net (code "66") (name "Net-(U$1-SS_TR)") (class "Default")
      (node (ref "C26") (pin "2") (pinfunction "2_2") (pintype "passive"))
      (node (ref "U$1") (pin "56") (pinfunction "SS_TR_56") (pintype "bidirectional"))
    )
    (net (code "67") (name "Net-(U$1-VSENSE)") (class "Default")
      (node (ref "R18") (pin "1") (pinfunction "1_1") (pintype "passive"))
      (node (ref "R19") (pin "2") (pinfunction "2_2") (pintype "passive"))
      (node (ref "U$1") (pin "3") (pinfunction "VSENSE_3") (pintype "bidirectional"))
    )
    (net (code "68") (name "Net-(U$3-PA0)") (class "Default")
      (node (ref "C28") (pin "1") (pinfunction "1_1") (pintype "passive"))
      (node (ref "R26") (pin "1") (pinfunction "1_1") (pintype "passive"))
      (node (ref "R27") (pin "2") (pinfunction "2_2") (pintype "passive"))
      (node (ref "U$3") (pin "14") (pinfunction "PA0_14") (pintype "bidirectional"))
    )
    (net (code "69") (name "Net-(U$3-PA4{slash}SPI1_NSS)") (class "Default")
      (node (ref "DA1") (pin "TP") (pinfunction "TP_TP") (pintype "input"))
      (node (ref "U$3") (pin "20") (pinfunction "PA4/SPI1_NSS_20") (pintype "bidirectional"))
    )
    (net (code "70") (name "Net-(U$3-PA5{slash}SPI1_SCK)") (class "Default")
      (node (ref "DA2") (pin "TP") (pinfunction "TP_TP") (pintype "input"))
      (node (ref "U$3") (pin "21") (pinfunction "PA5/SPI1_SCK_21") (pintype "bidirectional"))
    )
    (net (code "71") (name "Net-(U$3-VCAP1)") (class "Default")
      (node (ref "C9") (pin "2") (pinfunction "2_2") (pintype "passive"))
      (node (ref "U$3") (pin "30") (pinfunction "VCAP1_30") (pintype "bidirectional"))
    )
    (net (code "72") (name "Net-(U$3-VDDA)") (class "Default")
      (node (ref "CHOKE") (pin "2") (pinfunction "2_2") (pintype "passive"))
      (node (ref "U$3") (pin "13") (pinfunction "VDDA_13") (pintype "bidirectional"))
    )
    (net (code "73") (name "unconnected-(U$1-DC_CAL-Pad12)") (class "Default")
      (node (ref "U$1") (pin "12") (pinfunction "DC_CAL_12") (pintype "bidirectional"))
    )
    (net (code "74") (name "unconnected-(U$1-EN_BUCK-Pad55)") (class "Default")
      (node (ref "U$1") (pin "55") (pinfunction "EN_BUCK_55") (pintype "bidirectional"))
    )
    (net (code "75") (name "unconnected-(U$1-FAULT'-Pad6)") (class "Default")
      (node (ref "U$1") (pin "6") (pinfunction "FAULT'_6") (pintype "bidirectional"))
    )
    (net (code "76") (name "unconnected-(U$1-INL_A-Pad18)") (class "Default")
      (node (ref "U$1") (pin "18") (pinfunction "INL_A_18") (pintype "bidirectional"))
    )
    (net (code "77") (name "unconnected-(U$1-INL_B-Pad20)") (class "Default")
      (node (ref "U$1") (pin "20") (pinfunction "INL_B_20") (pintype "bidirectional"))
    )
    (net (code "78") (name "unconnected-(U$1-INL_C-Pad22)") (class "Default")
      (node (ref "U$1") (pin "22") (pinfunction "INL_C_22") (pintype "bidirectional"))
    )
    (net (code "79") (name "unconnected-(U$1-M_OC-Pad9)") (class "Default")
      (node (ref "U$1") (pin "9") (pinfunction "M_OC_9") (pintype "bidirectional"))
    )
    (net (code "80") (name "unconnected-(U$1-OCTW'-Pad5)") (class "Default")
      (node (ref "U$1") (pin "5") (pinfunction "OCTW'_5") (pintype "bidirectional"))
    )
    (net (code "81") (name "unconnected-(U$1-PWRGD-Pad4)") (class "Default")
      (node (ref "U$1") (pin "4") (pinfunction "PWRGD_4") (pintype "bidirectional"))
    )
    (net (code "82") (name "unconnected-(U$3-PA1-Pad15)") (class "Default")
      (node (ref "U$3") (pin "15") (pinfunction "PA1_15") (pintype "bidirectional"))
    )
    (net (code "83") (name "unconnected-(U$3-PA12-Pad45)") (class "Default")
      (node (ref "U$3") (pin "45") (pinfunction "PA12_45") (pintype "bidirectional"))
    )
    (net (code "84") (name "unconnected-(U$3-PB0-Pad26)") (class "Default")
      (node (ref "U$3") (pin "26") (pinfunction "PB0_26") (pintype "bidirectional"))
    )
    (net (code "85") (name "unconnected-(U$3-PB1-Pad27)") (class "Default")
      (node (ref "U$3") (pin "27") (pinfunction "PB1_27") (pintype "bidirectional"))
    )
    (net (code "86") (name "unconnected-(U$3-PB2-BOOT1-Pad28)") (class "Default")
      (node (ref "U$3") (pin "28") (pinfunction "PB2-BOOT1_28") (pintype "bidirectional"))
    )
    (net (code "87") (name "unconnected-(U$3-PB4{slash}JTRST-Pad56)") (class "Default")
      (node (ref "U$3") (pin "56") (pinfunction "PB4/JTRST_56") (pintype "bidirectional"))
    )
    (net (code "88") (name "unconnected-(U$3-PB5-Pad57)") (class "Default")
      (node (ref "U$3") (pin "57") (pinfunction "PB5_57") (pintype "bidirectional"))
    )
    (net (code "89") (name "unconnected-(U$3-PB10-Pad29)") (class "Default")
      (node (ref "U$3") (pin "29") (pinfunction "PB10_29") (pintype "bidirectional"))
    )
    (net (code "90") (name "unconnected-(U$3-PB12{slash}I2S2_WS-Pad33)") (class "Default")
      (node (ref "U$3") (pin "33") (pinfunction "PB12/I2S2_WS_33") (pintype "bidirectional"))
    )
    (net (code "91") (name "unconnected-(U$3-PB13{slash}I2S2_CK-Pad34)") (class "Default")
      (node (ref "U$3") (pin "34") (pinfunction "PB13/I2S2_CK_34") (pintype "bidirectional"))
    )
    (net (code "92") (name "unconnected-(U$3-PB14{slash}I2S2_XD-Pad35)") (class "Default")
      (node (ref "U$3") (pin "35") (pinfunction "PB14/I2S2_XD_35") (pintype "bidirectional"))
    )
    (net (code "93") (name "unconnected-(U$3-PB15{slash}I2S2_SD-Pad36)") (class "Default")
      (node (ref "U$3") (pin "36") (pinfunction "PB15/I2S2_SD_36") (pintype "bidirectional"))
    )
    (net (code "94") (name "unconnected-(U$3-PC2-Pad10)") (class "Default")
      (node (ref "U$3") (pin "10") (pinfunction "PC2_10") (pintype "bidirectional"))
    )
    (net (code "95") (name "unconnected-(U$3-PC3-Pad11)") (class "Default")
      (node (ref "U$3") (pin "11") (pinfunction "PC3_11") (pintype "bidirectional"))
    )
    (net (code "96") (name "unconnected-(U$3-PC5-Pad25)") (class "Default")
      (node (ref "U$3") (pin "25") (pinfunction "PC5_25") (pintype "bidirectional"))
    )
    (net (code "97") (name "unconnected-(U$3-PC6{slash}I2S2_MCK-Pad37)") (class "Default")
      (node (ref "U$3") (pin "37") (pinfunction "PC6/I2S2_MCK_37") (pintype "bidirectional"))
    )
    (net (code "98") (name "unconnected-(U$3-PC7-Pad38)") (class "Default")
      (node (ref "U$3") (pin "38") (pinfunction "PC7_38") (pintype "bidirectional"))
    )
    (net (code "99") (name "unconnected-(U$3-PC8{slash}SDIO_D0-Pad39)") (class "Default")
      (node (ref "U$3") (pin "39") (pinfunction "PC8/SDIO_D0_39") (pintype "bidirectional"))
    )
    (net (code "100") (name "unconnected-(U$3-PC9{slash}SDIO_D1-Pad40)") (class "Default")
      (node (ref "U$3") (pin "40") (pinfunction "PC9/SDIO_D1_40") (pintype "bidirectional"))
    )
    (net (code "101") (name "unconnected-(U$3-PC13-Pad2)") (class "Default")
      (node (ref "U$3") (pin "2") (pinfunction "PC13_2") (pintype "bidirectional"))
    )
    (net (code "102") (name "unconnected-(U$3-PC14-Pad3)") (class "Default")
      (node (ref "U$3") (pin "3") (pinfunction "PC14_3") (pintype "bidirectional"))
    )
    (net (code "103") (name "unconnected-(U$3-PC15-Pad4)") (class "Default")
      (node (ref "U$3") (pin "4") (pinfunction "PC15_4") (pintype "bidirectional"))
    )
    (net (code "104") (name "unconnected-(U$3-PD2{slash}SDIO_CMD-Pad54)") (class "Default")
      (node (ref "U$3") (pin "54") (pinfunction "PD2/SDIO_CMD_54") (pintype "bidirectional"))
    )
    (net (code "105") (name "unconnected-(U$3-PH1-Pad6)") (class "Default")
      (node (ref "U$3") (pin "6") (pinfunction "PH1_6") (pintype "bidirectional"))
    )
  )
)
